# TrackerBreakout.net
KiCad netlist of a schematic drawn in EAGLE
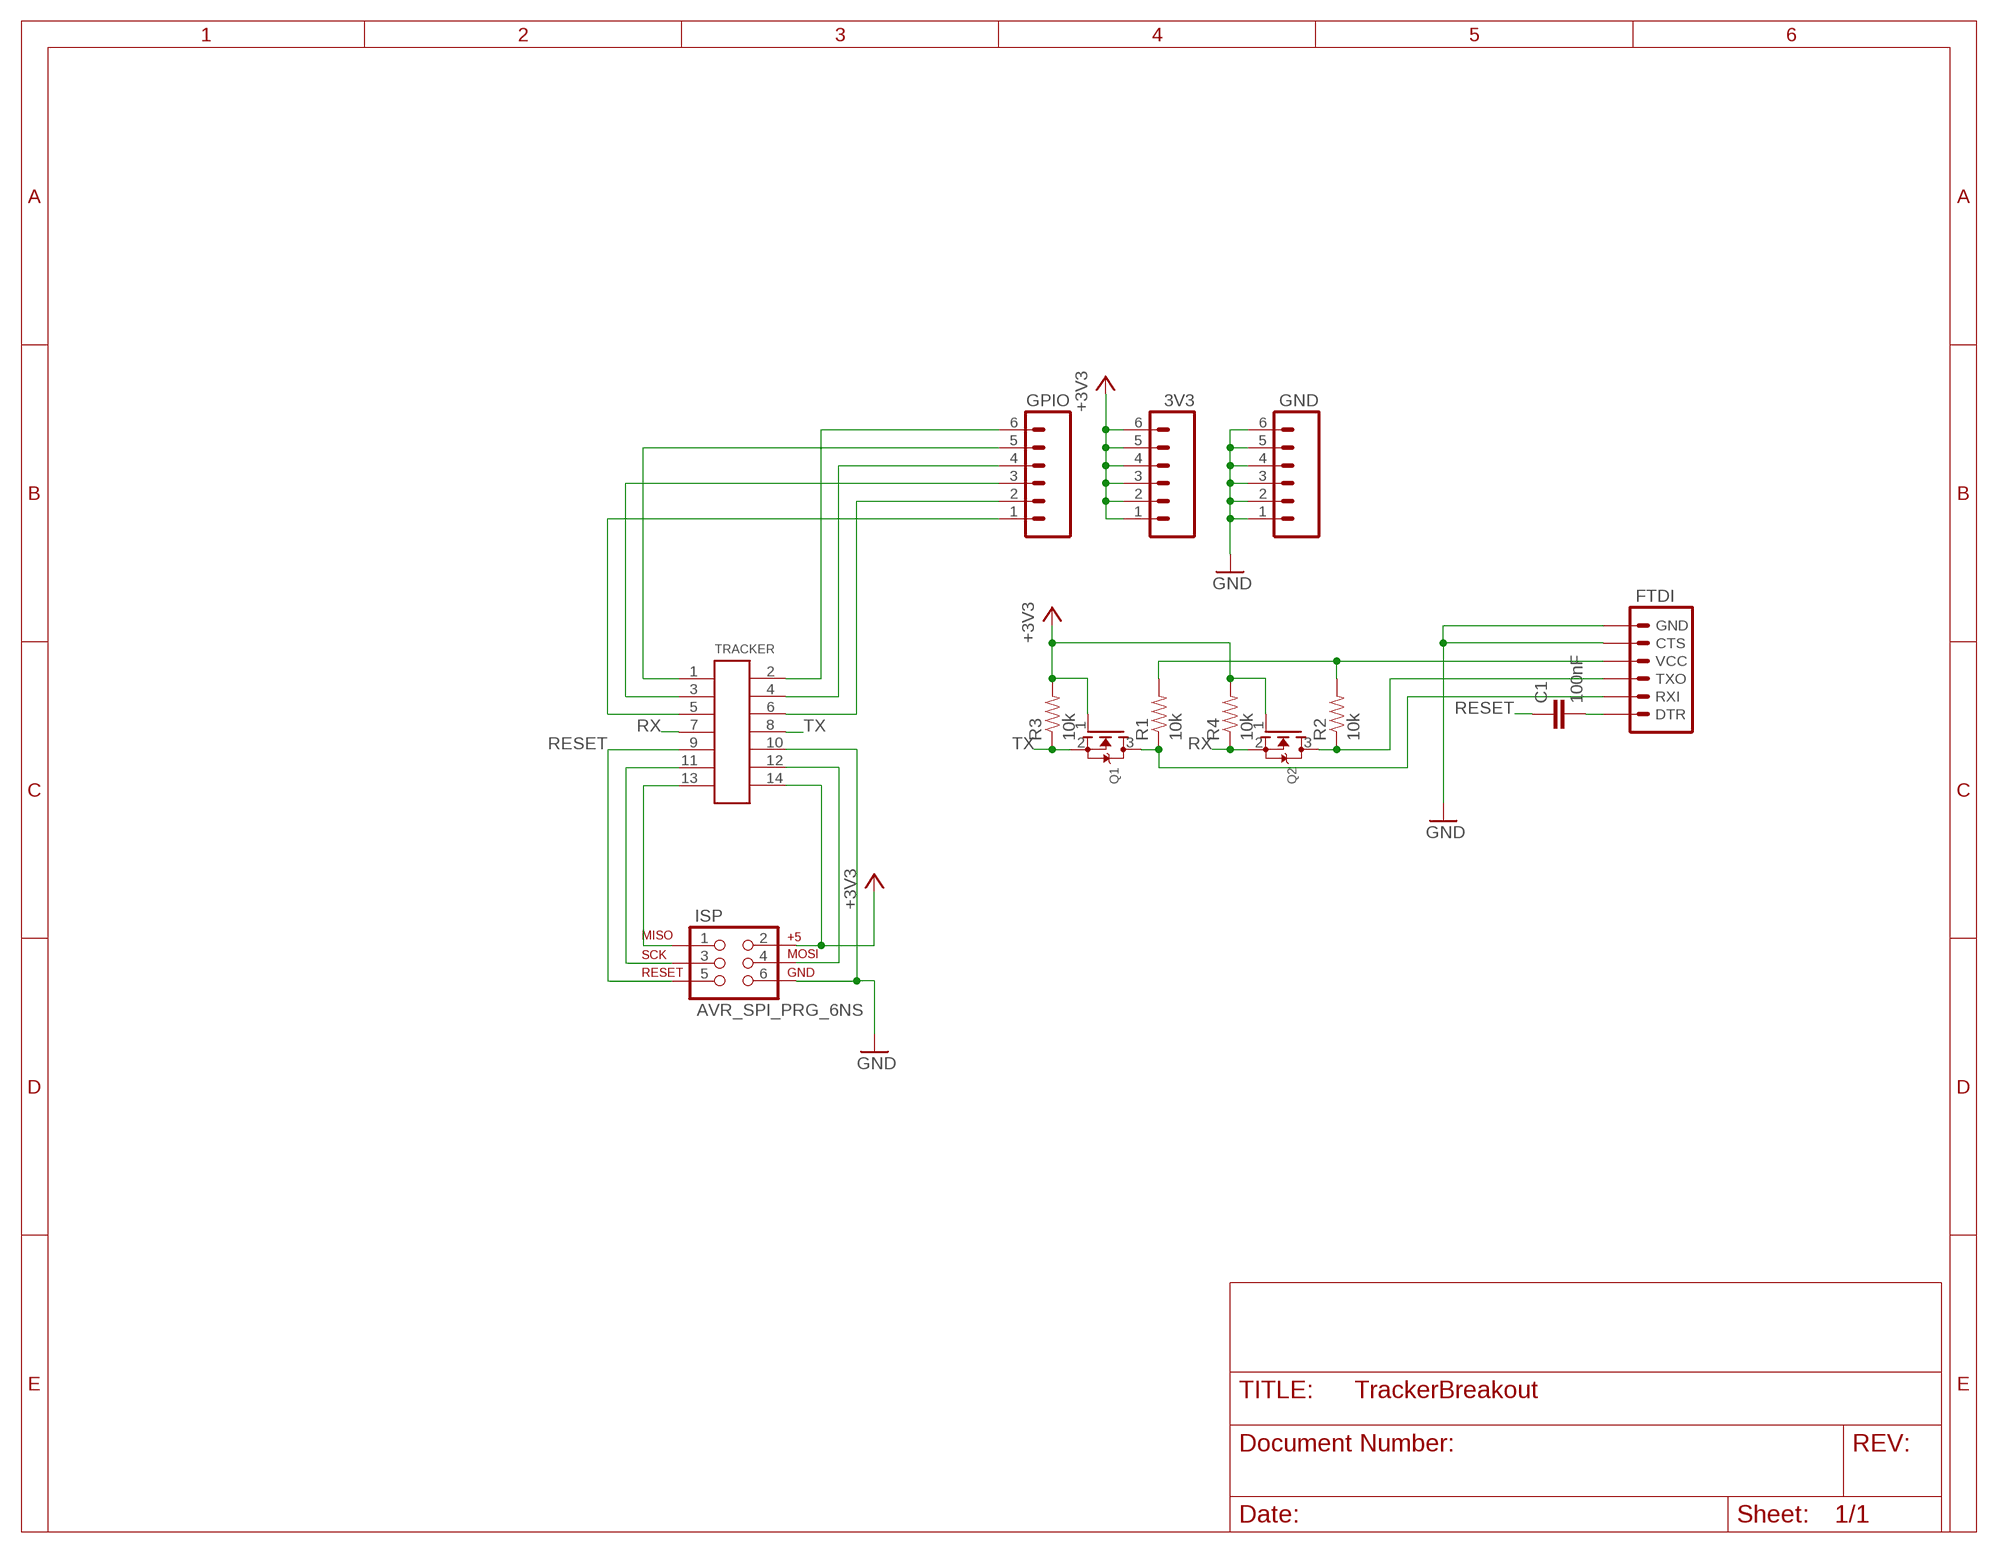
[diagram p0: schematic, sheet 1]

(export (version "E")
  (design (tool "Eeschema 10.0.6"))
  (components
    (comp (ref "3V3")
      (value "M06SIP")
      (footprint "eagle-import:1X06")
      (libsource (lib "eagle-import") (part "M06SIP"))
    )
    (comp (ref "C1")
      (value "100nF")
      (footprint "eagle-import:0402-CAP")
      (libsource (lib "eagle-import") (part "CAP0402-CAP"))
    )
    (comp (ref "FTDI")
      (value "ARDUINO_SERIAL_PROGRAMPTH")
      (footprint "eagle-import:1X06")
      (libsource (lib "eagle-import") (part "ARDUINO_SERIAL_PROGRAMPTH"))
    )
    (comp (ref "GND")
      (value "M06SIP")
      (footprint "eagle-import:1X06")
      (libsource (lib "eagle-import") (part "M06SIP"))
    )
    (comp (ref "GPIO")
      (value "M06SIP")
      (footprint "eagle-import:1X06")
      (libsource (lib "eagle-import") (part "M06SIP"))
    )
    (comp (ref "ISP")
      (value "AVR_SPI_PRG_6NS")
      (footprint "eagle-import:2X3-NS")
      (libsource (lib "eagle-import") (part "AVR_SPI_PRG_6NS"))
    )
    (comp (ref "Q1")
      (value "MOSFET-N")
      (footprint "eagle-import:SOT416")
      (libsource (lib "eagle-import") (part "MOSFET-N"))
    )
    (comp (ref "Q2")
      (value "MOSFET-N")
      (footprint "eagle-import:SOT416")
      (libsource (lib "eagle-import") (part "MOSFET-N"))
    )
    (comp (ref "R1")
      (value "10k")
      (footprint "eagle-import:0402-RES")
      (libsource (lib "eagle-import") (part "RESISTOR0402-RES"))
    )
    (comp (ref "R2")
      (value "10k")
      (footprint "eagle-import:0402-RES")
      (libsource (lib "eagle-import") (part "RESISTOR0402-RES"))
    )
    (comp (ref "R3")
      (value "10k")
      (footprint "eagle-import:0402-RES")
      (libsource (lib "eagle-import") (part "RESISTOR0402-RES"))
    )
    (comp (ref "R4")
      (value "10k")
      (footprint "eagle-import:0402-RES")
      (libsource (lib "eagle-import") (part "RESISTOR0402-RES"))
    )
    (comp (ref "TRACKER")
      (value "DF12A3.0-14DS")
      (footprint "eagle-import:DF12A3.0-14DS")
      (libsource (lib "eagle-import") (part "DF12A3.0-14DS"))
    )
  )
  (nets
    (net (code "1") (name "+3V3") (class "Default")
      (node (ref "3V3") (pin "1") (pinfunction "1_1") (pintype "passive"))
      (node (ref "3V3") (pin "2") (pinfunction "2_2") (pintype "passive"))
      (node (ref "3V3") (pin "3") (pinfunction "3_3") (pintype "passive"))
      (node (ref "3V3") (pin "4") (pinfunction "4_4") (pintype "passive"))
      (node (ref "3V3") (pin "5") (pinfunction "5_5") (pintype "passive"))
      (node (ref "3V3") (pin "6") (pinfunction "6_6") (pintype "passive"))
      (node (ref "ISP") (pin "2") (pinfunction "2_2") (pintype "passive"))
      (node (ref "Q1") (pin "1") (pinfunction "G_1") (pintype "bidirectional"))
      (node (ref "Q2") (pin "1") (pinfunction "G_1") (pintype "bidirectional"))
      (node (ref "R3") (pin "2") (pinfunction "2_2") (pintype "passive"))
      (node (ref "R4") (pin "2") (pinfunction "2_2") (pintype "passive"))
      (node (ref "TRACKER") (pin "14") (pinfunction "14_14") (pintype "bidirectional"))
    )
    (net (code "2") (name "/RESET") (class "Default")
      (node (ref "C1") (pin "1") (pinfunction "1_1") (pintype "passive"))
      (node (ref "ISP") (pin "5") (pinfunction "5_5") (pintype "passive"))
      (node (ref "TRACKER") (pin "9") (pinfunction "9_9") (pintype "bidirectional"))
    )
    (net (code "3") (name "/RX") (class "Default")
      (node (ref "Q2") (pin "2") (pinfunction "S_2") (pintype "bidirectional"))
      (node (ref "R4") (pin "1") (pinfunction "1_1") (pintype "passive"))
      (node (ref "TRACKER") (pin "7") (pinfunction "7_7") (pintype "bidirectional"))
    )
    (net (code "4") (name "/TX") (class "Default")
      (node (ref "Q1") (pin "2") (pinfunction "S_2") (pintype "bidirectional"))
      (node (ref "R3") (pin "1") (pinfunction "1_1") (pintype "passive"))
      (node (ref "TRACKER") (pin "8") (pinfunction "8_8") (pintype "bidirectional"))
    )
    (net (code "5") (name "GND") (class "Default")
      (node (ref "FTDI") (pin "5") (pinfunction "CTS_5") (pintype "passive"))
      (node (ref "FTDI") (pin "6") (pinfunction "GND_6") (pintype "passive"))
      (node (ref "GND") (pin "1") (pinfunction "1_1") (pintype "passive"))
      (node (ref "GND") (pin "2") (pinfunction "2_2") (pintype "passive"))
      (node (ref "GND") (pin "3") (pinfunction "3_3") (pintype "passive"))
      (node (ref "GND") (pin "4") (pinfunction "4_4") (pintype "passive"))
      (node (ref "GND") (pin "5") (pinfunction "5_5") (pintype "passive"))
      (node (ref "GND") (pin "6") (pinfunction "6_6") (pintype "passive"))
      (node (ref "ISP") (pin "6") (pinfunction "6_6") (pintype "passive"))
      (node (ref "TRACKER") (pin "10") (pinfunction "10_10") (pintype "bidirectional"))
    )
    (net (code "6") (name "Net-(FTDI-DTR)") (class "Default")
      (node (ref "C1") (pin "2") (pinfunction "2_2") (pintype "passive"))
      (node (ref "FTDI") (pin "1") (pinfunction "DTR_1") (pintype "passive"))
    )
    (net (code "7") (name "Net-(FTDI-RXI)") (class "Default")
      (node (ref "FTDI") (pin "2") (pinfunction "RXI_2") (pintype "passive"))
      (node (ref "Q1") (pin "3") (pinfunction "D_3") (pintype "bidirectional"))
      (node (ref "R1") (pin "1") (pinfunction "1_1") (pintype "passive"))
    )
    (net (code "8") (name "Net-(FTDI-TXO)") (class "Default")
      (node (ref "FTDI") (pin "3") (pinfunction "TXO_3") (pintype "passive"))
      (node (ref "Q2") (pin "3") (pinfunction "D_3") (pintype "bidirectional"))
      (node (ref "R2") (pin "1") (pinfunction "1_1") (pintype "passive"))
    )
    (net (code "9") (name "Net-(FTDI-VCC)") (class "Default")
      (node (ref "FTDI") (pin "4") (pinfunction "VCC_4") (pintype "passive"))
      (node (ref "R1") (pin "2") (pinfunction "2_2") (pintype "passive"))
      (node (ref "R2") (pin "2") (pinfunction "2_2") (pintype "passive"))
    )
    (net (code "10") (name "Net-(GPIO-Pad1)") (class "Default")
      (node (ref "GPIO") (pin "1") (pinfunction "1_1") (pintype "passive"))
      (node (ref "TRACKER") (pin "5") (pinfunction "5_5") (pintype "bidirectional"))
    )
    (net (code "11") (name "Net-(GPIO-Pad2)") (class "Default")
      (node (ref "GPIO") (pin "2") (pinfunction "2_2") (pintype "passive"))
      (node (ref "TRACKER") (pin "6") (pinfunction "6_6") (pintype "bidirectional"))
    )
    (net (code "12") (name "Net-(GPIO-Pad3)") (class "Default")
      (node (ref "GPIO") (pin "3") (pinfunction "3_3") (pintype "passive"))
      (node (ref "TRACKER") (pin "3") (pinfunction "3_3") (pintype "bidirectional"))
    )
    (net (code "13") (name "Net-(GPIO-Pad4)") (class "Default")
      (node (ref "GPIO") (pin "4") (pinfunction "4_4") (pintype "passive"))
      (node (ref "TRACKER") (pin "4") (pinfunction "4_4") (pintype "bidirectional"))
    )
    (net (code "14") (name "Net-(GPIO-Pad5)") (class "Default")
      (node (ref "GPIO") (pin "5") (pinfunction "5_5") (pintype "passive"))
      (node (ref "TRACKER") (pin "1") (pinfunction "1_1") (pintype "bidirectional"))
    )
    (net (code "15") (name "Net-(GPIO-Pad6)") (class "Default")
      (node (ref "GPIO") (pin "6") (pinfunction "6_6") (pintype "passive"))
      (node (ref "TRACKER") (pin "2") (pinfunction "2_2") (pintype "bidirectional"))
    )
    (net (code "16") (name "Net-(ISP-Pad1)") (class "Default")
      (node (ref "ISP") (pin "1") (pinfunction "1_1") (pintype "passive"))
      (node (ref "TRACKER") (pin "13") (pinfunction "13_13") (pintype "bidirectional"))
    )
    (net (code "17") (name "Net-(ISP-Pad3)") (class "Default")
      (node (ref "ISP") (pin "3") (pinfunction "3_3") (pintype "passive"))
      (node (ref "TRACKER") (pin "11") (pinfunction "11_11") (pintype "bidirectional"))
    )
    (net (code "18") (name "Net-(ISP-Pad4)") (class "Default")
      (node (ref "ISP") (pin "4") (pinfunction "4_4") (pintype "passive"))
      (node (ref "TRACKER") (pin "12") (pinfunction "12_12") (pintype "bidirectional"))
    )
  )
)
